# CMC_ECG.net
KiCad netlist of a schematic drawn in EAGLE
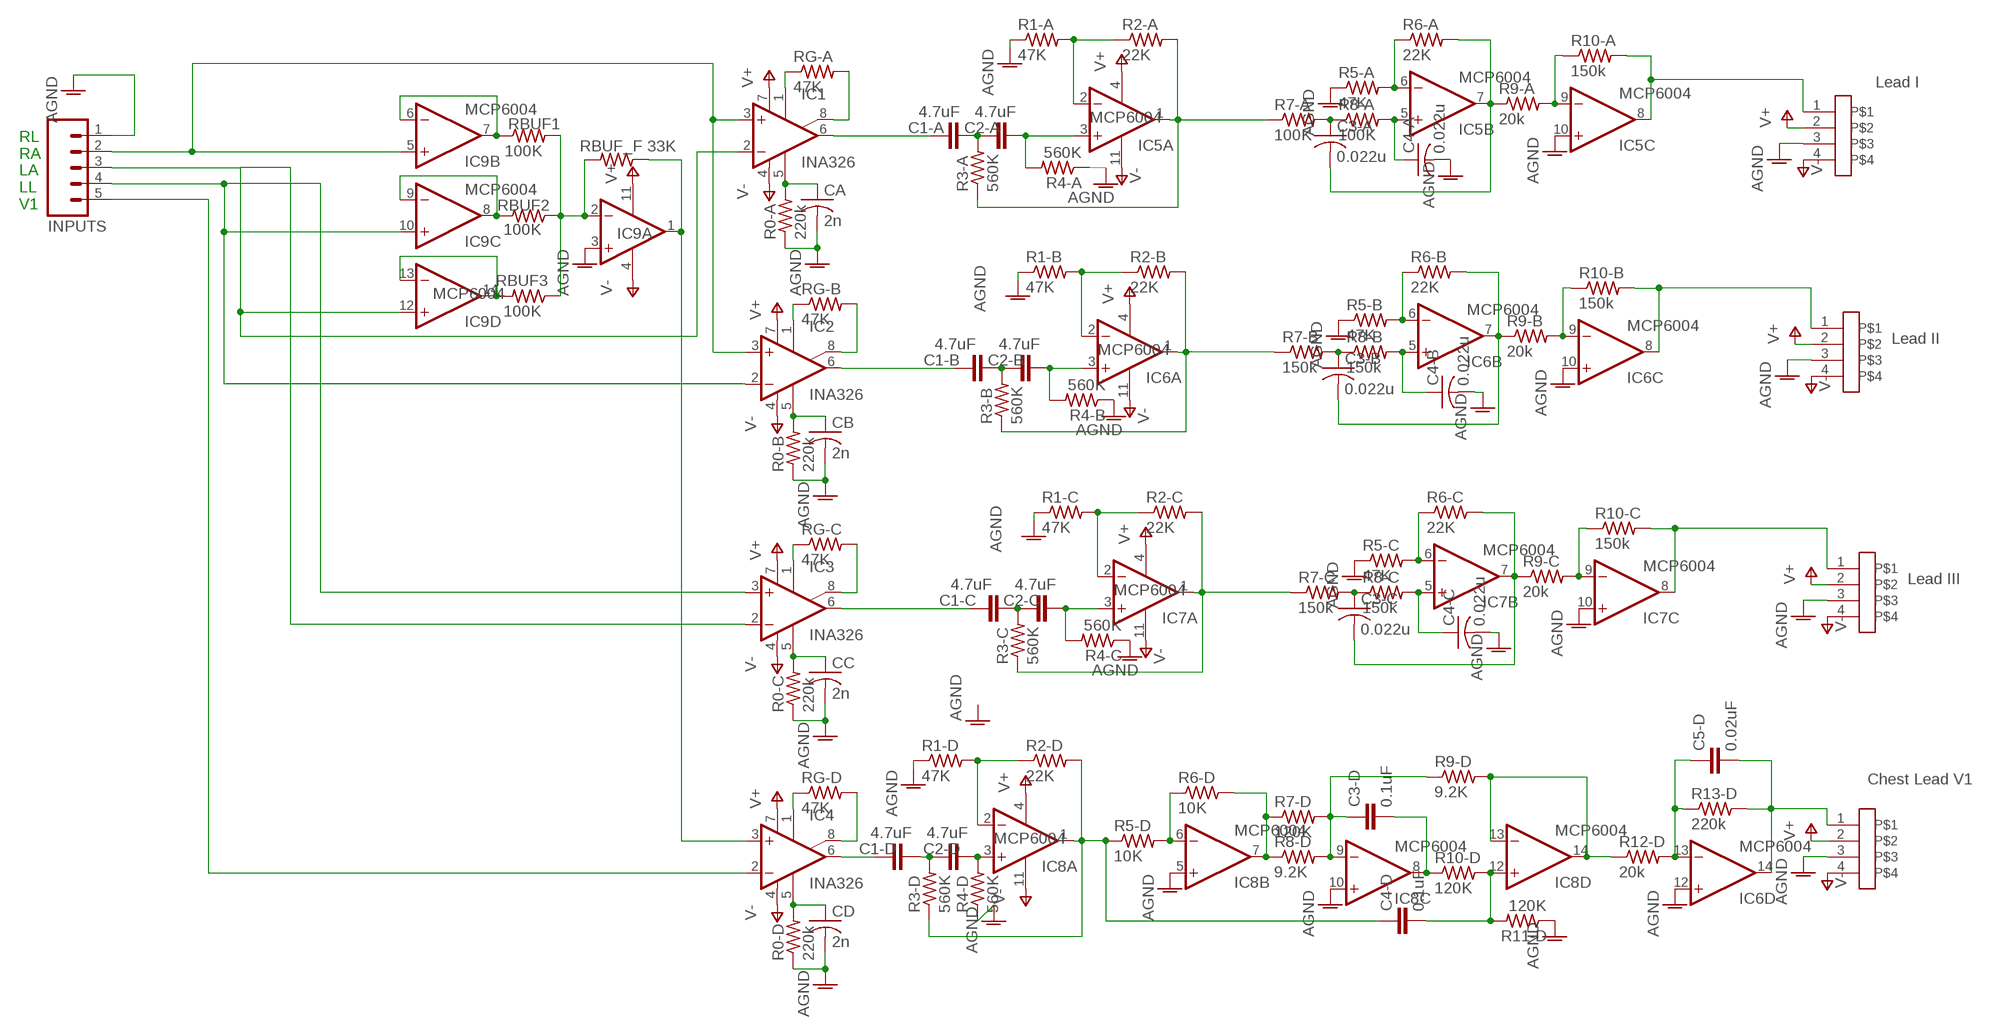
[diagram p0: schematic, sheet 1]

(export (version "E")
  (design (tool "Eeschema 10.0.6"))
  (components
    (comp (ref "C1-A")
      (value "4.7uF")
      (footprint "eagle-import:C0805")
      (libsource (lib "eagle-import") (part "C-EUC0805"))
    )
    (comp (ref "C1-B")
      (value "4.7uF")
      (footprint "eagle-import:C0805")
      (libsource (lib "eagle-import") (part "C-EUC0805"))
    )
    (comp (ref "C1-C")
      (value "4.7uF")
      (footprint "eagle-import:C0805")
      (libsource (lib "eagle-import") (part "C-EUC0805"))
    )
    (comp (ref "C1-D")
      (value "4.7uF")
      (footprint "eagle-import:C0805")
      (libsource (lib "eagle-import") (part "C-EUC0805"))
    )
    (comp (ref "C2-A")
      (value "4.7uF")
      (footprint "eagle-import:C0805")
      (libsource (lib "eagle-import") (part "C-EUC0805"))
    )
    (comp (ref "C2-B")
      (value "4.7uF")
      (footprint "eagle-import:C0805")
      (libsource (lib "eagle-import") (part "C-EUC0805"))
    )
    (comp (ref "C2-C")
      (value "4.7uF")
      (footprint "eagle-import:C0805")
      (libsource (lib "eagle-import") (part "C-EUC0805"))
    )
    (comp (ref "C2-D")
      (value "4.7uF")
      (footprint "eagle-import:C0805")
      (libsource (lib "eagle-import") (part "C-EUC0805"))
    )
    (comp (ref "C3-A")
      (value "0.022u")
      (footprint "eagle-import:C0805")
      (libsource (lib "eagle-import") (part "C-USC0805"))
    )
    (comp (ref "C3-B")
      (value "0.022u")
      (footprint "eagle-import:C0805")
      (libsource (lib "eagle-import") (part "C-USC0805"))
    )
    (comp (ref "C3-C")
      (value "0.022u")
      (footprint "eagle-import:C0805")
      (libsource (lib "eagle-import") (part "C-USC0805"))
    )
    (comp (ref "C3-D")
      (value "0.1uF")
      (footprint "eagle-import:C0805")
      (libsource (lib "eagle-import") (part "C-EUC0805"))
    )
    (comp (ref "C4-A")
      (value "0.022u")
      (footprint "eagle-import:C0805")
      (libsource (lib "eagle-import") (part "C-USC0805"))
    )
    (comp (ref "C4-B")
      (value "0.022u")
      (footprint "eagle-import:C0805")
      (libsource (lib "eagle-import") (part "C-USC0805"))
    )
    (comp (ref "C4-C")
      (value "0.022u")
      (footprint "eagle-import:C0805")
      (libsource (lib "eagle-import") (part "C-USC0805"))
    )
    (comp (ref "C4-D")
      (value "0.1uF")
      (footprint "eagle-import:C0805")
      (libsource (lib "eagle-import") (part "C-EUC0805"))
    )
    (comp (ref "C5-D")
      (value "0.02uF")
      (footprint "eagle-import:C0805")
      (libsource (lib "eagle-import") (part "C-EUC0805"))
    )
    (comp (ref "CA")
      (value "2n")
      (footprint "eagle-import:C0805")
      (libsource (lib "eagle-import") (part "C-USC0805"))
    )
    (comp (ref "CB")
      (value "2n")
      (footprint "eagle-import:C0805")
      (libsource (lib "eagle-import") (part "C-USC0805"))
    )
    (comp (ref "CC")
      (value "2n")
      (footprint "eagle-import:C0805")
      (libsource (lib "eagle-import") (part "C-USC0805"))
    )
    (comp (ref "CD")
      (value "2n")
      (footprint "eagle-import:C0805")
      (libsource (lib "eagle-import") (part "C-USC0805"))
    )
    (comp (ref "CHEST-V3")
      (value "CON-4PIN_SIL")
      (footprint "eagle-import:CON-4PIN-SIL")
      (libsource (lib "eagle-import") (part "CON-4PIN_SIL"))
    )
    (comp (ref "IC1")
      (value "INA326")
      (footprint "eagle-import:MSOP-08")
      (libsource (lib "eagle-import") (part "INA326"))
    )
    (comp (ref "IC2")
      (value "INA326")
      (footprint "eagle-import:MSOP-08")
      (libsource (lib "eagle-import") (part "INA326"))
    )
    (comp (ref "IC3")
      (value "INA326")
      (footprint "eagle-import:MSOP-08")
      (libsource (lib "eagle-import") (part "INA326"))
    )
    (comp (ref "IC4")
      (value "INA326")
      (footprint "eagle-import:MSOP-08")
      (libsource (lib "eagle-import") (part "INA326"))
    )
    (comp (ref "IC5")
      (value "MCP6004")
      (footprint "eagle-import:TSSOP14")
      (libsource (lib "eagle-import") (part "MCP604ST"))
    )
    (comp (ref "IC6")
      (value "MCP6004")
      (footprint "eagle-import:TSSOP14")
      (libsource (lib "eagle-import") (part "MCP604ST"))
    )
    (comp (ref "IC7")
      (value "MCP6004")
      (footprint "eagle-import:TSSOP14")
      (libsource (lib "eagle-import") (part "MCP604ST"))
    )
    (comp (ref "IC8")
      (value "MCP6004")
      (footprint "eagle-import:TSSOP14")
      (libsource (lib "eagle-import") (part "MCP604ST"))
    )
    (comp (ref "IC9")
      (value "MCP6004")
      (footprint "eagle-import:TSSOP14")
      (libsource (lib "eagle-import") (part "MCP604ST"))
    )
    (comp (ref "INPUTS")
      (value "M05")
      (footprint "eagle-import:05P")
      (libsource (lib "eagle-import") (part "M05"))
    )
    (comp (ref "LEAD-I")
      (value "CON-4PIN_SIL")
      (footprint "eagle-import:CON-4PIN-SIL")
      (libsource (lib "eagle-import") (part "CON-4PIN_SIL"))
    )
    (comp (ref "LEAD-II")
      (value "CON-4PIN_SIL")
      (footprint "eagle-import:CON-4PIN-SIL")
      (libsource (lib "eagle-import") (part "CON-4PIN_SIL"))
    )
    (comp (ref "LEAD-II1")
      (value "CON-4PIN_SIL")
      (footprint "eagle-import:CON-4PIN-SIL")
      (libsource (lib "eagle-import") (part "CON-4PIN_SIL"))
    )
    (comp (ref "R0-A")
      (value "220k")
      (footprint "eagle-import:R0805")
      (libsource (lib "eagle-import") (part "R-US_R0805"))
    )
    (comp (ref "R0-B")
      (value "220k")
      (footprint "eagle-import:R0805")
      (libsource (lib "eagle-import") (part "R-US_R0805"))
    )
    (comp (ref "R0-C")
      (value "220k")
      (footprint "eagle-import:R0805")
      (libsource (lib "eagle-import") (part "R-US_R0805"))
    )
    (comp (ref "R0-D")
      (value "220k")
      (footprint "eagle-import:R0805")
      (libsource (lib "eagle-import") (part "R-US_R0805"))
    )
    (comp (ref "R1-A")
      (value "47K")
      (footprint "eagle-import:R0805")
      (libsource (lib "eagle-import") (part "R-US_R0805"))
    )
    (comp (ref "R1-B")
      (value "47K")
      (footprint "eagle-import:R0805")
      (libsource (lib "eagle-import") (part "R-US_R0805"))
    )
    (comp (ref "R1-C")
      (value "47K")
      (footprint "eagle-import:R0805")
      (libsource (lib "eagle-import") (part "R-US_R0805"))
    )
    (comp (ref "R1-D")
      (value "47K")
      (footprint "eagle-import:R0805")
      (libsource (lib "eagle-import") (part "R-US_R0805"))
    )
    (comp (ref "R2-A")
      (value "22K")
      (footprint "eagle-import:R0805")
      (libsource (lib "eagle-import") (part "R-US_R0805"))
    )
    (comp (ref "R2-B")
      (value "22K")
      (footprint "eagle-import:R0805")
      (libsource (lib "eagle-import") (part "R-US_R0805"))
    )
    (comp (ref "R2-C")
      (value "22K")
      (footprint "eagle-import:R0805")
      (libsource (lib "eagle-import") (part "R-US_R0805"))
    )
    (comp (ref "R2-D")
      (value "22K")
      (footprint "eagle-import:R0805")
      (libsource (lib "eagle-import") (part "R-US_R0805"))
    )
    (comp (ref "R3-A")
      (value "560K")
      (footprint "eagle-import:R0805")
      (libsource (lib "eagle-import") (part "R-US_R0805"))
    )
    (comp (ref "R3-B")
      (value "560K")
      (footprint "eagle-import:R0805")
      (libsource (lib "eagle-import") (part "R-US_R0805"))
    )
    (comp (ref "R3-C")
      (value "560K")
      (footprint "eagle-import:R0805")
      (libsource (lib "eagle-import") (part "R-US_R0805"))
    )
    (comp (ref "R3-D")
      (value "560K")
      (footprint "eagle-import:R0805")
      (libsource (lib "eagle-import") (part "R-US_R0805"))
    )
    (comp (ref "R4-A")
      (value "560K")
      (footprint "eagle-import:R0805")
      (libsource (lib "eagle-import") (part "R-US_R0805"))
    )
    (comp (ref "R4-B")
      (value "560K")
      (footprint "eagle-import:R0805")
      (libsource (lib "eagle-import") (part "R-US_R0805"))
    )
    (comp (ref "R4-C")
      (value "560K")
      (footprint "eagle-import:R0805")
      (libsource (lib "eagle-import") (part "R-US_R0805"))
    )
    (comp (ref "R4-D")
      (value "560K")
      (footprint "eagle-import:R0805")
      (libsource (lib "eagle-import") (part "R-US_R0805"))
    )
    (comp (ref "R5-A")
      (value "47K")
      (footprint "eagle-import:R0805")
      (libsource (lib "eagle-import") (part "R-US_R0805"))
    )
    (comp (ref "R5-B")
      (value "47K")
      (footprint "eagle-import:R0805")
      (libsource (lib "eagle-import") (part "R-US_R0805"))
    )
    (comp (ref "R5-C")
      (value "47K")
      (footprint "eagle-import:R0805")
      (libsource (lib "eagle-import") (part "R-US_R0805"))
    )
    (comp (ref "R5-D")
      (value "10K")
      (footprint "eagle-import:R0805")
      (libsource (lib "eagle-import") (part "R-US_R0805"))
    )
    (comp (ref "R6-A")
      (value "22K")
      (footprint "eagle-import:R0805")
      (libsource (lib "eagle-import") (part "R-US_R0805"))
    )
    (comp (ref "R6-B")
      (value "22K")
      (footprint "eagle-import:R0805")
      (libsource (lib "eagle-import") (part "R-US_R0805"))
    )
    (comp (ref "R6-C")
      (value "22K")
      (footprint "eagle-import:R0805")
      (libsource (lib "eagle-import") (part "R-US_R0805"))
    )
    (comp (ref "R6-D")
      (value "10K")
      (footprint "eagle-import:R0805")
      (libsource (lib "eagle-import") (part "R-US_R0805"))
    )
    (comp (ref "R7-A")
      (value "100K")
      (footprint "eagle-import:R0805")
      (libsource (lib "eagle-import") (part "R-US_R0805"))
    )
    (comp (ref "R7-B")
      (value "150k")
      (footprint "eagle-import:R0805")
      (libsource (lib "eagle-import") (part "R-US_R0805"))
    )
    (comp (ref "R7-C")
      (value "150k")
      (footprint "eagle-import:R0805")
      (libsource (lib "eagle-import") (part "R-US_R0805"))
    )
    (comp (ref "R7-D")
      (value "120K")
      (footprint "eagle-import:R0805")
      (libsource (lib "eagle-import") (part "R-US_R0805"))
    )
    (comp (ref "R8-A")
      (value "100K")
      (footprint "eagle-import:R0805")
      (libsource (lib "eagle-import") (part "R-US_R0805"))
    )
    (comp (ref "R8-B")
      (value "150k")
      (footprint "eagle-import:R0805")
      (libsource (lib "eagle-import") (part "R-US_R0805"))
    )
    (comp (ref "R8-C")
      (value "150k")
      (footprint "eagle-import:R0805")
      (libsource (lib "eagle-import") (part "R-US_R0805"))
    )
    (comp (ref "R8-D")
      (value "9.2K")
      (footprint "eagle-import:R0805")
      (libsource (lib "eagle-import") (part "R-US_R0805"))
    )
    (comp (ref "R9-A")
      (value "20k")
      (footprint "eagle-import:R0805")
      (libsource (lib "eagle-import") (part "R-US_R0805"))
    )
    (comp (ref "R9-B")
      (value "20k")
      (footprint "eagle-import:R0805")
      (libsource (lib "eagle-import") (part "R-US_R0805"))
    )
    (comp (ref "R9-C")
      (value "20k")
      (footprint "eagle-import:R0805")
      (libsource (lib "eagle-import") (part "R-US_R0805"))
    )
    (comp (ref "R9-D")
      (value "9.2K")
      (footprint "eagle-import:R0805")
      (libsource (lib "eagle-import") (part "R-US_R0805"))
    )
    (comp (ref "R10-A")
      (value "150k")
      (footprint "eagle-import:R0805")
      (libsource (lib "eagle-import") (part "R-US_R0805"))
    )
    (comp (ref "R10-B")
      (value "150k")
      (footprint "eagle-import:R0805")
      (libsource (lib "eagle-import") (part "R-US_R0805"))
    )
    (comp (ref "R10-C")
      (value "150k")
      (footprint "eagle-import:R0805")
      (libsource (lib "eagle-import") (part "R-US_R0805"))
    )
    (comp (ref "R10-D")
      (value "120K")
      (footprint "eagle-import:R0805")
      (libsource (lib "eagle-import") (part "R-US_R0805"))
    )
    (comp (ref "R11-D")
      (value "120K")
      (footprint "eagle-import:R0805")
      (libsource (lib "eagle-import") (part "R-US_R0805"))
    )
    (comp (ref "R12-D")
      (value "20k")
      (footprint "eagle-import:R0805")
      (libsource (lib "eagle-import") (part "R-US_R0805"))
    )
    (comp (ref "R13-D")
      (value "220k")
      (footprint "eagle-import:R0805")
      (libsource (lib "eagle-import") (part "R-US_R0805"))
    )
    (comp (ref "RBUF1")
      (value "100K")
      (footprint "eagle-import:R0805")
      (libsource (lib "eagle-import") (part "R-US_R0805"))
    )
    (comp (ref "RBUF2")
      (value "100K")
      (footprint "eagle-import:R0805")
      (libsource (lib "eagle-import") (part "R-US_R0805"))
    )
    (comp (ref "RBUF3")
      (value "100K")
      (footprint "eagle-import:R0805")
      (libsource (lib "eagle-import") (part "R-US_R0805"))
    )
    (comp (ref "RBUF_F")
      (value "33K")
      (footprint "eagle-import:R0805")
      (libsource (lib "eagle-import") (part "R-US_R0805"))
    )
    (comp (ref "RG-A")
      (value "47K")
      (footprint "eagle-import:R0805")
      (libsource (lib "eagle-import") (part "R-US_R0805"))
    )
    (comp (ref "RG-B")
      (value "47K")
      (footprint "eagle-import:R0805")
      (libsource (lib "eagle-import") (part "R-US_R0805"))
    )
    (comp (ref "RG-C")
      (value "47K")
      (footprint "eagle-import:R0805")
      (libsource (lib "eagle-import") (part "R-US_R0805"))
    )
    (comp (ref "RG-D")
      (value "47K")
      (footprint "eagle-import:R0805")
      (libsource (lib "eagle-import") (part "R-US_R0805"))
    )
  )
  (nets
    (net (code "1") (name "AGND") (class "Default")
      (node (ref "C4-A") (pin "2") (pinfunction "2_2") (pintype "passive"))
      (node (ref "C4-B") (pin "2") (pinfunction "2_2") (pintype "passive"))
      (node (ref "C4-C") (pin "2") (pinfunction "2_2") (pintype "passive"))
      (node (ref "CA") (pin "2") (pinfunction "2_2") (pintype "passive"))
      (node (ref "CB") (pin "2") (pinfunction "2_2") (pintype "passive"))
      (node (ref "CC") (pin "2") (pinfunction "2_2") (pintype "passive"))
      (node (ref "CD") (pin "2") (pinfunction "2_2") (pintype "passive"))
      (node (ref "CHEST-V3") (pin "3") (pinfunction "P$3_3") (pintype "bidirectional"))
      (node (ref "IC5") (pin "10") (pinfunction "+IN_10") (pintype "input"))
      (node (ref "IC6") (pin "10") (pinfunction "+IN_10") (pintype "input"))
      (node (ref "IC6") (pin "12") (pinfunction "+IN_12") (pintype "input"))
      (node (ref "IC7") (pin "10") (pinfunction "+IN_10") (pintype "input"))
      (node (ref "IC8") (pin "10") (pinfunction "+IN_10") (pintype "input"))
      (node (ref "IC8") (pin "5") (pinfunction "+IN_5") (pintype "input"))
      (node (ref "IC9") (pin "3") (pinfunction "+IN_3") (pintype "input"))
      (node (ref "INPUTS") (pin "1") (pinfunction "1_1") (pintype "passive"))
      (node (ref "LEAD-I") (pin "3") (pinfunction "P$3_3") (pintype "bidirectional"))
      (node (ref "LEAD-II") (pin "3") (pinfunction "P$3_3") (pintype "bidirectional"))
      (node (ref "LEAD-II1") (pin "3") (pinfunction "P$3_3") (pintype "bidirectional"))
      (node (ref "R0-A") (pin "1") (pinfunction "1_1") (pintype "passive"))
      (node (ref "R0-B") (pin "1") (pinfunction "1_1") (pintype "passive"))
      (node (ref "R0-C") (pin "1") (pinfunction "1_1") (pintype "passive"))
      (node (ref "R0-D") (pin "1") (pinfunction "1_1") (pintype "passive"))
      (node (ref "R1-A") (pin "1") (pinfunction "1_1") (pintype "passive"))
      (node (ref "R1-B") (pin "1") (pinfunction "1_1") (pintype "passive"))
      (node (ref "R1-C") (pin "1") (pinfunction "1_1") (pintype "passive"))
      (node (ref "R1-D") (pin "1") (pinfunction "1_1") (pintype "passive"))
      (node (ref "R11-D") (pin "1") (pinfunction "1_1") (pintype "passive"))
      (node (ref "R4-A") (pin "1") (pinfunction "1_1") (pintype "passive"))
      (node (ref "R4-B") (pin "1") (pinfunction "1_1") (pintype "passive"))
      (node (ref "R4-C") (pin "1") (pinfunction "1_1") (pintype "passive"))
      (node (ref "R4-D") (pin "1") (pinfunction "1_1") (pintype "passive"))
      (node (ref "R5-A") (pin "1") (pinfunction "1_1") (pintype "passive"))
      (node (ref "R5-B") (pin "1") (pinfunction "1_1") (pintype "passive"))
      (node (ref "R5-C") (pin "1") (pinfunction "1_1") (pintype "passive"))
    )
    (net (code "2") (name "Net-(C1-A-Pad2)") (class "Default")
      (node (ref "C1-A") (pin "2") (pinfunction "2_2") (pintype "passive"))
      (node (ref "C2-A") (pin "1") (pinfunction "1_1") (pintype "passive"))
      (node (ref "R3-A") (pin "2") (pinfunction "2_2") (pintype "passive"))
    )
    (net (code "3") (name "Net-(C1-B-Pad2)") (class "Default")
      (node (ref "C1-B") (pin "2") (pinfunction "2_2") (pintype "passive"))
      (node (ref "C2-B") (pin "1") (pinfunction "1_1") (pintype "passive"))
      (node (ref "R3-B") (pin "2") (pinfunction "2_2") (pintype "passive"))
    )
    (net (code "4") (name "Net-(C1-C-Pad2)") (class "Default")
      (node (ref "C1-C") (pin "2") (pinfunction "2_2") (pintype "passive"))
      (node (ref "C2-C") (pin "1") (pinfunction "1_1") (pintype "passive"))
      (node (ref "R3-C") (pin "2") (pinfunction "2_2") (pintype "passive"))
    )
    (net (code "5") (name "Net-(C1-D-Pad2)") (class "Default")
      (node (ref "C1-D") (pin "2") (pinfunction "2_2") (pintype "passive"))
      (node (ref "C2-D") (pin "1") (pinfunction "1_1") (pintype "passive"))
      (node (ref "R3-D") (pin "2") (pinfunction "2_2") (pintype "passive"))
    )
    (net (code "6") (name "Net-(C3-A-Pad1)") (class "Default")
      (node (ref "C3-A") (pin "1") (pinfunction "1_1") (pintype "passive"))
      (node (ref "R7-A") (pin "2") (pinfunction "2_2") (pintype "passive"))
      (node (ref "R8-A") (pin "1") (pinfunction "1_1") (pintype "passive"))
    )
    (net (code "7") (name "Net-(C3-B-Pad1)") (class "Default")
      (node (ref "C3-B") (pin "1") (pinfunction "1_1") (pintype "passive"))
      (node (ref "R7-B") (pin "2") (pinfunction "2_2") (pintype "passive"))
      (node (ref "R8-B") (pin "1") (pinfunction "1_1") (pintype "passive"))
    )
    (net (code "8") (name "Net-(C3-C-Pad1)") (class "Default")
      (node (ref "C3-C") (pin "1") (pinfunction "1_1") (pintype "passive"))
      (node (ref "R7-C") (pin "2") (pinfunction "2_2") (pintype "passive"))
      (node (ref "R8-C") (pin "1") (pinfunction "1_1") (pintype "passive"))
    )
    (net (code "9") (name "Net-(CHEST-V3-P$1)") (class "Default")
      (node (ref "C5-D") (pin "2") (pinfunction "2_2") (pintype "passive"))
      (node (ref "CHEST-V3") (pin "1") (pinfunction "P$1_1") (pintype "bidirectional"))
      (node (ref "IC6") (pin "14") (pinfunction "OUT_14") (pintype "output"))
      (node (ref "R13-D") (pin "2") (pinfunction "2_2") (pintype "passive"))
    )
    (net (code "10") (name "Net-(IC1-+IN)") (class "Default")
      (node (ref "IC1") (pin "3") (pinfunction "+IN_3") (pintype "input"))
      (node (ref "IC2") (pin "3") (pinfunction "+IN_3") (pintype "input"))
      (node (ref "IC9") (pin "5") (pinfunction "+IN_5") (pintype "input"))
      (node (ref "INPUTS") (pin "2") (pinfunction "2_2") (pintype "passive"))
    )
    (net (code "11") (name "Net-(IC1--IN)") (class "Default")
      (node (ref "IC1") (pin "2") (pinfunction "-IN_2") (pintype "input"))
      (node (ref "IC3") (pin "2") (pinfunction "-IN_2") (pintype "input"))
      (node (ref "IC9") (pin "12") (pinfunction "+IN_12") (pintype "input"))
      (node (ref "INPUTS") (pin "3") (pinfunction "3_3") (pintype "passive"))
    )
    (net (code "12") (name "Net-(IC1-OUT)") (class "Default")
      (node (ref "C1-A") (pin "1") (pinfunction "1_1") (pintype "passive"))
      (node (ref "IC1") (pin "6") (pinfunction "OUT_6") (pintype "output"))
    )
    (net (code "13") (name "Net-(IC1-R1)") (class "Default")
      (node (ref "IC1") (pin "1") (pinfunction "R1_1") (pintype "passive"))
      (node (ref "RG-A") (pin "1") (pinfunction "1_1") (pintype "passive"))
    )
    (net (code "14") (name "Net-(IC1-R1B)") (class "Default")
      (node (ref "IC1") (pin "8") (pinfunction "R1B_8") (pintype "passive"))
      (node (ref "RG-A") (pin "2") (pinfunction "2_2") (pintype "passive"))
    )
    (net (code "15") (name "Net-(IC1-R2)") (class "Default")
      (node (ref "CA") (pin "1") (pinfunction "1_1") (pintype "passive"))
      (node (ref "IC1") (pin "5") (pinfunction "R2_5") (pintype "passive"))
      (node (ref "R0-A") (pin "2") (pinfunction "2_2") (pintype "passive"))
    )
    (net (code "16") (name "Net-(IC2--IN)") (class "Default")
      (node (ref "IC2") (pin "2") (pinfunction "-IN_2") (pintype "input"))
      (node (ref "IC3") (pin "3") (pinfunction "+IN_3") (pintype "input"))
      (node (ref "IC9") (pin "10") (pinfunction "+IN_10") (pintype "input"))
      (node (ref "INPUTS") (pin "4") (pinfunction "4_4") (pintype "passive"))
    )
    (net (code "17") (name "Net-(IC2-OUT)") (class "Default")
      (node (ref "C1-B") (pin "1") (pinfunction "1_1") (pintype "passive"))
      (node (ref "IC2") (pin "6") (pinfunction "OUT_6") (pintype "output"))
    )
    (net (code "18") (name "Net-(IC2-R1)") (class "Default")
      (node (ref "IC2") (pin "1") (pinfunction "R1_1") (pintype "passive"))
      (node (ref "RG-B") (pin "1") (pinfunction "1_1") (pintype "passive"))
    )
    (net (code "19") (name "Net-(IC2-R1B)") (class "Default")
      (node (ref "IC2") (pin "8") (pinfunction "R1B_8") (pintype "passive"))
      (node (ref "RG-B") (pin "2") (pinfunction "2_2") (pintype "passive"))
    )
    (net (code "20") (name "Net-(IC2-R2)") (class "Default")
      (node (ref "CB") (pin "1") (pinfunction "1_1") (pintype "passive"))
      (node (ref "IC2") (pin "5") (pinfunction "R2_5") (pintype "passive"))
      (node (ref "R0-B") (pin "2") (pinfunction "2_2") (pintype "passive"))
    )
    (net (code "21") (name "Net-(IC3-OUT)") (class "Default")
      (node (ref "C1-C") (pin "1") (pinfunction "1_1") (pintype "passive"))
      (node (ref "IC3") (pin "6") (pinfunction "OUT_6") (pintype "output"))
    )
    (net (code "22") (name "Net-(IC3-R1)") (class "Default")
      (node (ref "IC3") (pin "1") (pinfunction "R1_1") (pintype "passive"))
      (node (ref "RG-C") (pin "1") (pinfunction "1_1") (pintype "passive"))
    )
    (net (code "23") (name "Net-(IC3-R1B)") (class "Default")
      (node (ref "IC3") (pin "8") (pinfunction "R1B_8") (pintype "passive"))
      (node (ref "RG-C") (pin "2") (pinfunction "2_2") (pintype "passive"))
    )
    (net (code "24") (name "Net-(IC3-R2)") (class "Default")
      (node (ref "CC") (pin "1") (pinfunction "1_1") (pintype "passive"))
      (node (ref "IC3") (pin "5") (pinfunction "R2_5") (pintype "passive"))
      (node (ref "R0-C") (pin "2") (pinfunction "2_2") (pintype "passive"))
    )
    (net (code "25") (name "Net-(IC4-+IN)") (class "Default")
      (node (ref "IC4") (pin "3") (pinfunction "+IN_3") (pintype "input"))
      (node (ref "IC9") (pin "1") (pinfunction "OUT_1") (pintype "output"))
      (node (ref "RBUF_F") (pin "1") (pinfunction "1_1") (pintype "passive"))
    )
    (net (code "26") (name "Net-(IC4--IN)") (class "Default")
      (node (ref "IC4") (pin "2") (pinfunction "-IN_2") (pintype "input"))
      (node (ref "INPUTS") (pin "5") (pinfunction "5_5") (pintype "passive"))
    )
    (net (code "27") (name "Net-(IC4-OUT)") (class "Default")
      (node (ref "C1-D") (pin "1") (pinfunction "1_1") (pintype "passive"))
      (node (ref "IC4") (pin "6") (pinfunction "OUT_6") (pintype "output"))
    )
    (net (code "28") (name "Net-(IC4-R1)") (class "Default")
      (node (ref "IC4") (pin "1") (pinfunction "R1_1") (pintype "passive"))
      (node (ref "RG-D") (pin "1") (pinfunction "1_1") (pintype "passive"))
    )
    (net (code "29") (name "Net-(IC4-R1B)") (class "Default")
      (node (ref "IC4") (pin "8") (pinfunction "R1B_8") (pintype "passive"))
      (node (ref "RG-D") (pin "2") (pinfunction "2_2") (pintype "passive"))
    )
    (net (code "30") (name "Net-(IC4-R2)") (class "Default")
      (node (ref "CD") (pin "1") (pinfunction "1_1") (pintype "passive"))
      (node (ref "IC4") (pin "5") (pinfunction "R2_5") (pintype "passive"))
      (node (ref "R0-D") (pin "2") (pinfunction "2_2") (pintype "passive"))
    )
    (net (code "31") (name "Net-(IC5A-+IN)") (class "Default")
      (node (ref "C2-A") (pin "2") (pinfunction "2_2") (pintype "passive"))
      (node (ref "IC5") (pin "3") (pinfunction "+IN_3") (pintype "input"))
      (node (ref "R4-A") (pin "2") (pinfunction "2_2") (pintype "passive"))
    )
    (net (code "32") (name "Net-(IC5A--IN)") (class "Default")
      (node (ref "IC5") (pin "2") (pinfunction "-IN_2") (pintype "input"))
      (node (ref "R1-A") (pin "2") (pinfunction "2_2") (pintype "passive"))
      (node (ref "R2-A") (pin "1") (pinfunction "1_1") (pintype "passive"))
    )
    (net (code "33") (name "Net-(IC5A-OUT)") (class "Default")
      (node (ref "IC5") (pin "1") (pinfunction "OUT_1") (pintype "output"))
      (node (ref "R2-A") (pin "2") (pinfunction "2_2") (pintype "passive"))
      (node (ref "R3-A") (pin "1") (pinfunction "1_1") (pintype "passive"))
      (node (ref "R7-A") (pin "1") (pinfunction "1_1") (pintype "passive"))
    )
    (net (code "34") (name "Net-(IC5B-+IN)") (class "Default")
      (node (ref "C4-A") (pin "1") (pinfunction "1_1") (pintype "passive"))
      (node (ref "IC5") (pin "5") (pinfunction "+IN_5") (pintype "input"))
      (node (ref "R8-A") (pin "2") (pinfunction "2_2") (pintype "passive"))
    )
    (net (code "35") (name "Net-(IC5B--IN)") (class "Default")
      (node (ref "IC5") (pin "6") (pinfunction "-IN_6") (pintype "input"))
      (node (ref "R5-A") (pin "2") (pinfunction "2_2") (pintype "passive"))
      (node (ref "R6-A") (pin "1") (pinfunction "1_1") (pintype "passive"))
    )
    (net (code "36") (name "Net-(IC5B-OUT)") (class "Default")
      (node (ref "C3-A") (pin "2") (pinfunction "2_2") (pintype "passive"))
      (node (ref "IC5") (pin "7") (pinfunction "OUT_7") (pintype "output"))
      (node (ref "R6-A") (pin "2") (pinfunction "2_2") (pintype "passive"))
      (node (ref "R9-A") (pin "1") (pinfunction "1_1") (pintype "passive"))
    )
    (net (code "37") (name "Net-(IC5C--IN)") (class "Default")
      (node (ref "IC5") (pin "9") (pinfunction "-IN_9") (pintype "input"))
      (node (ref "R10-A") (pin "1") (pinfunction "1_1") (pintype "passive"))
      (node (ref "R9-A") (pin "2") (pinfunction "2_2") (pintype "passive"))
    )
    (net (code "38") (name "Net-(IC5C-OUT)") (class "Default")
      (node (ref "IC5") (pin "8") (pinfunction "OUT_8") (pintype "output"))
      (node (ref "LEAD-I") (pin "1") (pinfunction "P$1_1") (pintype "bidirectional"))
      (node (ref "R10-A") (pin "2") (pinfunction "2_2") (pintype "passive"))
    )
    (net (code "39") (name "Net-(IC6A-+IN)") (class "Default")
      (node (ref "C2-B") (pin "2") (pinfunction "2_2") (pintype "passive"))
      (node (ref "IC6") (pin "3") (pinfunction "+IN_3") (pintype "input"))
      (node (ref "R4-B") (pin "2") (pinfunction "2_2") (pintype "passive"))
    )
    (net (code "40") (name "Net-(IC6A--IN)") (class "Default")
      (node (ref "IC6") (pin "2") (pinfunction "-IN_2") (pintype "input"))
      (node (ref "R1-B") (pin "2") (pinfunction "2_2") (pintype "passive"))
      (node (ref "R2-B") (pin "1") (pinfunction "1_1") (pintype "passive"))
    )
    (net (code "41") (name "Net-(IC6A-OUT)") (class "Default")
      (node (ref "IC6") (pin "1") (pinfunction "OUT_1") (pintype "output"))
      (node (ref "R2-B") (pin "2") (pinfunction "2_2") (pintype "passive"))
      (node (ref "R3-B") (pin "1") (pinfunction "1_1") (pintype "passive"))
      (node (ref "R7-B") (pin "1") (pinfunction "1_1") (pintype "passive"))
    )
    (net (code "42") (name "Net-(IC6B-+IN)") (class "Default")
      (node (ref "C4-B") (pin "1") (pinfunction "1_1") (pintype "passive"))
      (node (ref "IC6") (pin "5") (pinfunction "+IN_5") (pintype "input"))
      (node (ref "R8-B") (pin "2") (pinfunction "2_2") (pintype "passive"))
    )
    (net (code "43") (name "Net-(IC6B--IN)") (class "Default")
      (node (ref "IC6") (pin "6") (pinfunction "-IN_6") (pintype "input"))
      (node (ref "R5-B") (pin "2") (pinfunction "2_2") (pintype "passive"))
      (node (ref "R6-B") (pin "1") (pinfunction "1_1") (pintype "passive"))
    )
    (net (code "44") (name "Net-(IC6B-OUT)") (class "Default")
      (node (ref "C3-B") (pin "2") (pinfunction "2_2") (pintype "passive"))
      (node (ref "IC6") (pin "7") (pinfunction "OUT_7") (pintype "output"))
      (node (ref "R6-B") (pin "2") (pinfunction "2_2") (pintype "passive"))
      (node (ref "R9-B") (pin "1") (pinfunction "1_1") (pintype "passive"))
    )
    (net (code "45") (name "Net-(IC6C--IN)") (class "Default")
      (node (ref "IC6") (pin "9") (pinfunction "-IN_9") (pintype "input"))
      (node (ref "R10-B") (pin "1") (pinfunction "1_1") (pintype "passive"))
      (node (ref "R9-B") (pin "2") (pinfunction "2_2") (pintype "passive"))
    )
    (net (code "46") (name "Net-(IC6C-OUT)") (class "Default")
      (node (ref "IC6") (pin "8") (pinfunction "OUT_8") (pintype "output"))
      (node (ref "LEAD-II") (pin "1") (pinfunction "P$1_1") (pintype "bidirectional"))
      (node (ref "R10-B") (pin "2") (pinfunction "2_2") (pintype "passive"))
    )
    (net (code "47") (name "Net-(IC6D--IN)") (class "Default")
      (node (ref "C5-D") (pin "1") (pinfunction "1_1") (pintype "passive"))
      (node (ref "IC6") (pin "13") (pinfunction "-IN_13") (pintype "input"))
      (node (ref "R12-D") (pin "2") (pinfunction "2_2") (pintype "passive"))
      (node (ref "R13-D") (pin "1") (pinfunction "1_1") (pintype "passive"))
    )
    (net (code "48") (name "Net-(IC7A-+IN)") (class "Default")
      (node (ref "C2-C") (pin "2") (pinfunction "2_2") (pintype "passive"))
      (node (ref "IC7") (pin "3") (pinfunction "+IN_3") (pintype "input"))
      (node (ref "R4-C") (pin "2") (pinfunction "2_2") (pintype "passive"))
    )
    (net (code "49") (name "Net-(IC7A--IN)") (class "Default")
      (node (ref "IC7") (pin "2") (pinfunction "-IN_2") (pintype "input"))
      (node (ref "R1-C") (pin "2") (pinfunction "2_2") (pintype "passive"))
      (node (ref "R2-C") (pin "1") (pinfunction "1_1") (pintype "passive"))
    )
    (net (code "50") (name "Net-(IC7A-OUT)") (class "Default")
      (node (ref "IC7") (pin "1") (pinfunction "OUT_1") (pintype "output"))
      (node (ref "R2-C") (pin "2") (pinfunction "2_2") (pintype "passive"))
      (node (ref "R3-C") (pin "1") (pinfunction "1_1") (pintype "passive"))
      (node (ref "R7-C") (pin "1") (pinfunction "1_1") (pintype "passive"))
    )
    (net (code "51") (name "Net-(IC7B-+IN)") (class "Default")
      (node (ref "C4-C") (pin "1") (pinfunction "1_1") (pintype "passive"))
      (node (ref "IC7") (pin "5") (pinfunction "+IN_5") (pintype "input"))
      (node (ref "R8-C") (pin "2") (pinfunction "2_2") (pintype "passive"))
    )
    (net (code "52") (name "Net-(IC7B--IN)") (class "Default")
      (node (ref "IC7") (pin "6") (pinfunction "-IN_6") (pintype "input"))
      (node (ref "R5-C") (pin "2") (pinfunction "2_2") (pintype "passive"))
      (node (ref "R6-C") (pin "1") (pinfunction "1_1") (pintype "passive"))
    )
    (net (code "53") (name "Net-(IC7B-OUT)") (class "Default")
      (node (ref "C3-C") (pin "2") (pinfunction "2_2") (pintype "passive"))
      (node (ref "IC7") (pin "7") (pinfunction "OUT_7") (pintype "output"))
      (node (ref "R6-C") (pin "2") (pinfunction "2_2") (pintype "passive"))
      (node (ref "R9-C") (pin "1") (pinfunction "1_1") (pintype "passive"))
    )
    (net (code "54") (name "Net-(IC7C--IN)") (class "Default")
      (node (ref "IC7") (pin "9") (pinfunction "-IN_9") (pintype "input"))
      (node (ref "R10-C") (pin "1") (pinfunction "1_1") (pintype "passive"))
      (node (ref "R9-C") (pin "2") (pinfunction "2_2") (pintype "passive"))
    )
    (net (code "55") (name "Net-(IC7C-OUT)") (class "Default")
      (node (ref "IC7") (pin "8") (pinfunction "OUT_8") (pintype "output"))
      (node (ref "LEAD-II1") (pin "1") (pinfunction "P$1_1") (pintype "bidirectional"))
      (node (ref "R10-C") (pin "2") (pinfunction "2_2") (pintype "passive"))
    )
    (net (code "56") (name "Net-(IC8A-+IN)") (class "Default")
      (node (ref "C2-D") (pin "2") (pinfunction "2_2") (pintype "passive"))
      (node (ref "IC8") (pin "3") (pinfunction "+IN_3") (pintype "input"))
      (node (ref "R4-D") (pin "2") (pinfunction "2_2") (pintype "passive"))
    )
    (net (code "57") (name "Net-(IC8A--IN)") (class "Default")
      (node (ref "IC8") (pin "2") (pinfunction "-IN_2") (pintype "input"))
      (node (ref "R1-D") (pin "2") (pinfunction "2_2") (pintype "passive"))
      (node (ref "R2-D") (pin "1") (pinfunction "1_1") (pintype "passive"))
    )
    (net (code "58") (name "Net-(IC8A-OUT)") (class "Default")
      (node (ref "C4-D") (pin "1") (pinfunction "1_1") (pintype "passive"))
      (node (ref "IC8") (pin "1") (pinfunction "OUT_1") (pintype "output"))
      (node (ref "R2-D") (pin "2") (pinfunction "2_2") (pintype "passive"))
      (node (ref "R3-D") (pin "1") (pinfunction "1_1") (pintype "passive"))
      (node (ref "R5-D") (pin "1") (pinfunction "1_1") (pintype "passive"))
    )
    (net (code "59") (name "Net-(IC8B--IN)") (class "Default")
      (node (ref "IC8") (pin "6") (pinfunction "-IN_6") (pintype "input"))
      (node (ref "R5-D") (pin "2") (pinfunction "2_2") (pintype "passive"))
      (node (ref "R6-D") (pin "1") (pinfunction "1_1") (pintype "passive"))
    )
    (net (code "60") (name "Net-(IC8B-OUT)") (class "Default")
      (node (ref "IC8") (pin "7") (pinfunction "OUT_7") (pintype "output"))
      (node (ref "R6-D") (pin "2") (pinfunction "2_2") (pintype "passive"))
      (node (ref "R7-D") (pin "1") (pinfunction "1_1") (pintype "passive"))
      (node (ref "R8-D") (pin "1") (pinfunction "1_1") (pintype "passive"))
    )
    (net (code "61") (name "Net-(IC8C--IN)") (class "Default")
      (node (ref "C3-D") (pin "1") (pinfunction "1_1") (pintype "passive"))
      (node (ref "IC8") (pin "9") (pinfunction "-IN_9") (pintype "input"))
      (node (ref "R7-D") (pin "2") (pinfunction "2_2") (pintype "passive"))
      (node (ref "R8-D") (pin "2") (pinfunction "2_2") (pintype "passive"))
      (node (ref "R9-D") (pin "1") (pinfunction "1_1") (pintype "passive"))
    )
    (net (code "62") (name "Net-(IC8C-OUT)") (class "Default")
      (node (ref "C3-D") (pin "2") (pinfunction "2_2") (pintype "passive"))
      (node (ref "IC8") (pin "8") (pinfunction "OUT_8") (pintype "output"))
      (node (ref "R10-D") (pin "1") (pinfunction "1_1") (pintype "passive"))
    )
    (net (code "63") (name "Net-(IC8D-+IN)") (class "Default")
      (node (ref "C4-D") (pin "2") (pinfunction "2_2") (pintype "passive"))
      (node (ref "IC8") (pin "12") (pinfunction "+IN_12") (pintype "input"))
      (node (ref "R10-D") (pin "2") (pinfunction "2_2") (pintype "passive"))
      (node (ref "R11-D") (pin "2") (pinfunction "2_2") (pintype "passive"))
    )
    (net (code "64") (name "Net-(IC8D--IN)") (class "Default")
      (node (ref "IC8") (pin "13") (pinfunction "-IN_13") (pintype "input"))
      (node (ref "IC8") (pin "14") (pinfunction "OUT_14") (pintype "output"))
      (node (ref "R12-D") (pin "1") (pinfunction "1_1") (pintype "passive"))
      (node (ref "R9-D") (pin "2") (pinfunction "2_2") (pintype "passive"))
    )
    (net (code "65") (name "Net-(IC9A--IN)") (class "Default")
      (node (ref "IC9") (pin "2") (pinfunction "-IN_2") (pintype "input"))
      (node (ref "RBUF1") (pin "2") (pinfunction "2_2") (pintype "passive"))
      (node (ref "RBUF2") (pin "1") (pinfunction "1_1") (pintype "passive"))
      (node (ref "RBUF3") (pin "1") (pinfunction "1_1") (pintype "passive"))
      (node (ref "RBUF_F") (pin "2") (pinfunction "2_2") (pintype "passive"))
    )
    (net (code "66") (name "Net-(IC9B--IN)") (class "Default")
      (node (ref "IC9") (pin "6") (pinfunction "-IN_6") (pintype "input"))
      (node (ref "IC9") (pin "7") (pinfunction "OUT_7") (pintype "output"))
      (node (ref "RBUF1") (pin "1") (pinfunction "1_1") (pintype "passive"))
    )
    (net (code "67") (name "Net-(IC9C--IN)") (class "Default")
      (node (ref "IC9") (pin "8") (pinfunction "OUT_8") (pintype "output"))
      (node (ref "IC9") (pin "9") (pinfunction "-IN_9") (pintype "input"))
      (node (ref "RBUF2") (pin "2") (pinfunction "2_2") (pintype "passive"))
    )
    (net (code "68") (name "Net-(IC9D--IN)") (class "Default")
      (node (ref "IC9") (pin "13") (pinfunction "-IN_13") (pintype "input"))
      (node (ref "IC9") (pin "14") (pinfunction "OUT_14") (pintype "output"))
      (node (ref "RBUF3") (pin "2") (pinfunction "2_2") (pintype "passive"))
    )
    (net (code "69") (name "V+") (class "Default")
      (node (ref "CHEST-V3") (pin "2") (pinfunction "P$2_2") (pintype "bidirectional"))
      (node (ref "IC1") (pin "7") (pinfunction "+VS_7") (pintype "power_in"))
      (node (ref "IC2") (pin "7") (pinfunction "+VS_7") (pintype "power_in"))
      (node (ref "IC3") (pin "7") (pinfunction "+VS_7") (pintype "power_in"))
      (node (ref "IC4") (pin "7") (pinfunction "+VS_7") (pintype "power_in"))
      (node (ref "IC5") (pin "4") (pinfunction "V+_4") (pintype "power_in"))
      (node (ref "IC6") (pin "4") (pinfunction "V+_4") (pintype "power_in"))
      (node (ref "IC7") (pin "4") (pinfunction "V+_4") (pintype "power_in"))
      (node (ref "IC8") (pin "4") (pinfunction "V+_4") (pintype "power_in"))
      (node (ref "IC9") (pin "11") (pinfunction "V-_11") (pintype "power_in"))
      (node (ref "LEAD-I") (pin "2") (pinfunction "P$2_2") (pintype "bidirectional"))
      (node (ref "LEAD-II") (pin "2") (pinfunction "P$2_2") (pintype "bidirectional"))
      (node (ref "LEAD-II1") (pin "2") (pinfunction "P$2_2") (pintype "bidirectional"))
    )
    (net (code "70") (name "V-") (class "Default")
      (node (ref "CHEST-V3") (pin "4") (pinfunction "P$4_4") (pintype "bidirectional"))
      (node (ref "IC1") (pin "4") (pinfunction "-VS_4") (pintype "power_in"))
      (node (ref "IC2") (pin "4") (pinfunction "-VS_4") (pintype "power_in"))
      (node (ref "IC3") (pin "4") (pinfunction "-VS_4") (pintype "power_in"))
      (node (ref "IC4") (pin "4") (pinfunction "-VS_4") (pintype "power_in"))
      (node (ref "IC5") (pin "11") (pinfunction "V-_11") (pintype "power_in"))
      (node (ref "IC6") (pin "11") (pinfunction "V-_11") (pintype "power_in"))
      (node (ref "IC7") (pin "11") (pinfunction "V-_11") (pintype "power_in"))
      (node (ref "IC8") (pin "11") (pinfunction "V-_11") (pintype "power_in"))
      (node (ref "IC9") (pin "4") (pinfunction "V+_4") (pintype "power_in"))
      (node (ref "LEAD-I") (pin "4") (pinfunction "P$4_4") (pintype "bidirectional"))
      (node (ref "LEAD-II") (pin "4") (pinfunction "P$4_4") (pintype "bidirectional"))
      (node (ref "LEAD-II1") (pin "4") (pinfunction "P$4_4") (pintype "bidirectional"))
    )
  )
)
